# main_board.net
KiCad netlist of a schematic drawn in EAGLE
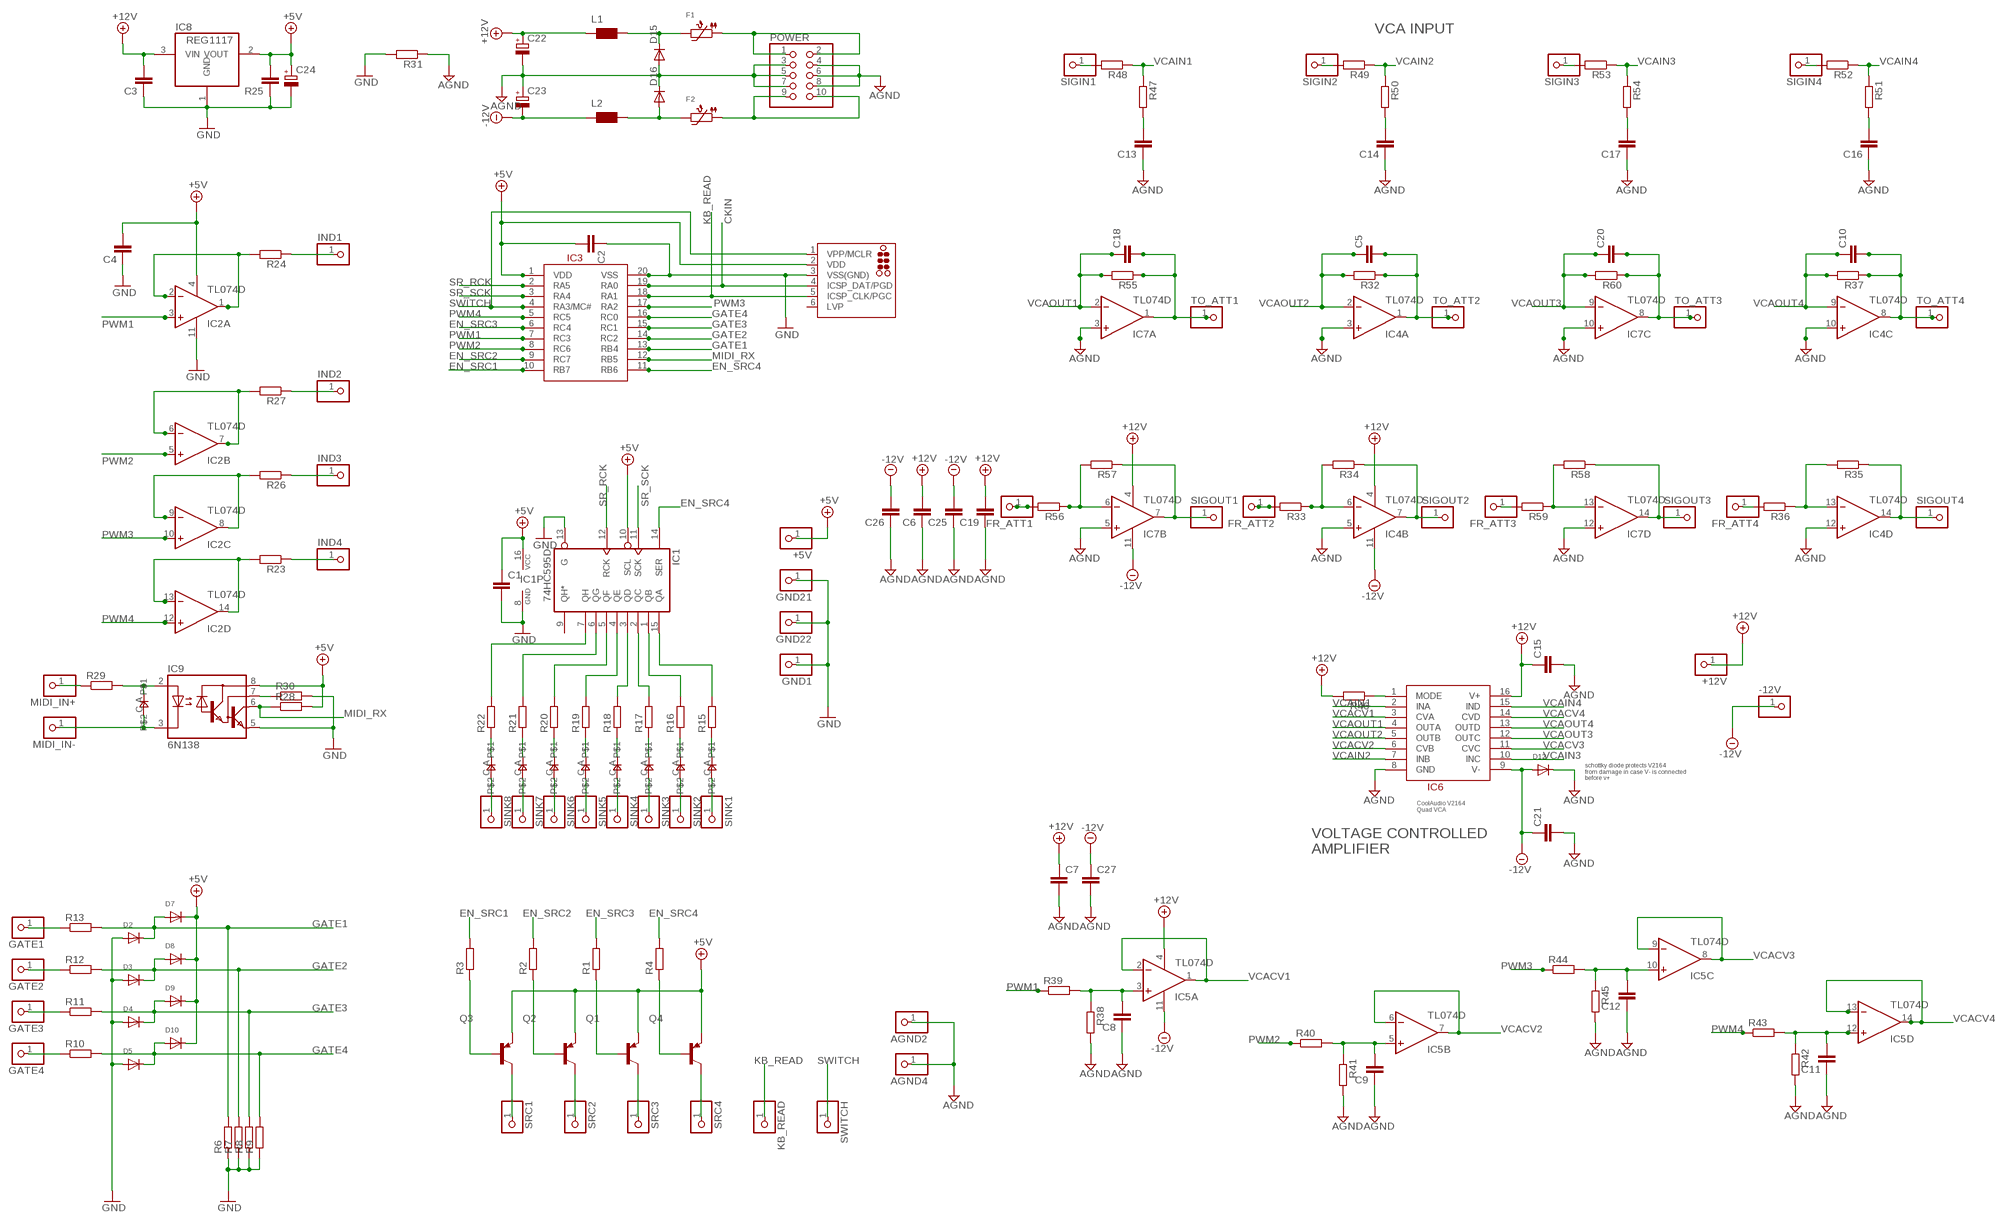
[diagram p0: schematic, sheet 1]

(export (version "E")
  (design (tool "Eeschema 10.0.6"))
  (components
    (comp (ref "+5V")
      (value "PINHD-1X1")
      (footprint "eagle-import:1X01")
      (libsource (lib "eagle-import") (part "PINHD-1X1"))
    )
    (comp (ref "+12V")
      (value "PINHD-1X1")
      (footprint "eagle-import:1X01")
      (libsource (lib "eagle-import") (part "PINHD-1X1"))
    )
    (comp (ref "-12V")
      (value "PINHD-1X1")
      (footprint "eagle-import:1X01")
      (libsource (lib "eagle-import") (part "PINHD-1X1"))
    )
    (comp (ref "AGND2")
      (value "PINHD-1X1")
      (footprint "eagle-import:1X01")
      (libsource (lib "eagle-import") (part "PINHD-1X1"))
    )
    (comp (ref "AGND4")
      (value "PINHD-1X1")
      (footprint "eagle-import:1X01")
      (libsource (lib "eagle-import") (part "PINHD-1X1"))
    )
    (comp (ref "C1")
      (value "C-EUC0805")
      (footprint "eagle-import:C0805")
      (libsource (lib "eagle-import") (part "C-EUC0805"))
    )
    (comp (ref "C2")
      (value "C-EUC0805")
      (footprint "eagle-import:C0805")
      (libsource (lib "eagle-import") (part "C-EUC0805"))
    )
    (comp (ref "C3")
      (value "C-EUC0805")
      (footprint "eagle-import:C0805")
      (libsource (lib "eagle-import") (part "C-EUC0805"))
    )
    (comp (ref "C4")
      (value "C-EUC0805")
      (footprint "eagle-import:C0805")
      (libsource (lib "eagle-import") (part "C-EUC0805"))
    )
    (comp (ref "C5")
      (value "C-EUC0805")
      (footprint "eagle-import:C0805")
      (libsource (lib "eagle-import") (part "C-EUC0805"))
    )
    (comp (ref "C6")
      (value "C-EUC0805")
      (footprint "eagle-import:C0805")
      (libsource (lib "eagle-import") (part "C-EUC0805"))
    )
    (comp (ref "C7")
      (value "C-EUC0805")
      (footprint "eagle-import:C0805")
      (libsource (lib "eagle-import") (part "C-EUC0805"))
    )
    (comp (ref "C8")
      (value "C-EUC0805")
      (footprint "eagle-import:C0805")
      (libsource (lib "eagle-import") (part "C-EUC0805"))
    )
    (comp (ref "C9")
      (value "C-EUC0805")
      (footprint "eagle-import:C0805")
      (libsource (lib "eagle-import") (part "C-EUC0805"))
    )
    (comp (ref "C10")
      (value "C-EUC0805")
      (footprint "eagle-import:C0805")
      (libsource (lib "eagle-import") (part "C-EUC0805"))
    )
    (comp (ref "C11")
      (value "C-EUC0805")
      (footprint "eagle-import:C0805")
      (libsource (lib "eagle-import") (part "C-EUC0805"))
    )
    (comp (ref "C12")
      (value "C-EUC0805")
      (footprint "eagle-import:C0805")
      (libsource (lib "eagle-import") (part "C-EUC0805"))
    )
    (comp (ref "C13")
      (value "C-EUC0805")
      (footprint "eagle-import:C0805")
      (libsource (lib "eagle-import") (part "C-EUC0805"))
    )
    (comp (ref "C14")
      (value "C-EUC0805")
      (footprint "eagle-import:C0805")
      (libsource (lib "eagle-import") (part "C-EUC0805"))
    )
    (comp (ref "C15")
      (value "C-EUC0805")
      (footprint "eagle-import:C0805")
      (libsource (lib "eagle-import") (part "C-EUC0805"))
    )
    (comp (ref "C16")
      (value "C-EUC0805")
      (footprint "eagle-import:C0805")
      (libsource (lib "eagle-import") (part "C-EUC0805"))
    )
    (comp (ref "C17")
      (value "C-EUC0805")
      (footprint "eagle-import:C0805")
      (libsource (lib "eagle-import") (part "C-EUC0805"))
    )
    (comp (ref "C18")
      (value "C-EUC0805")
      (footprint "eagle-import:C0805")
      (libsource (lib "eagle-import") (part "C-EUC0805"))
    )
    (comp (ref "C19")
      (value "C-EUC0805")
      (footprint "eagle-import:C0805")
      (libsource (lib "eagle-import") (part "C-EUC0805"))
    )
    (comp (ref "C20")
      (value "C-EUC0805")
      (footprint "eagle-import:C0805")
      (libsource (lib "eagle-import") (part "C-EUC0805"))
    )
    (comp (ref "C21")
      (value "C-EUC0805")
      (footprint "eagle-import:C0805")
      (libsource (lib "eagle-import") (part "C-EUC0805"))
    )
    (comp (ref "C22")
      (value "CPOL-EUE2.5-7")
      (footprint "eagle-import:E2,5-7")
      (libsource (lib "eagle-import") (part "CPOL-EUE2.5-7"))
    )
    (comp (ref "C23")
      (value "CPOL-EUE2.5-7")
      (footprint "eagle-import:E2,5-7")
      (libsource (lib "eagle-import") (part "CPOL-EUE2.5-7"))
    )
    (comp (ref "C24")
      (value "CPOL-EUE2.5-5")
      (footprint "eagle-import:E2,5-5")
      (libsource (lib "eagle-import") (part "CPOL-EUE2.5-5"))
    )
    (comp (ref "C25")
      (value "C-EUC0805")
      (footprint "eagle-import:C0805")
      (libsource (lib "eagle-import") (part "C-EUC0805"))
    )
    (comp (ref "C26")
      (value "C-EUC0805")
      (footprint "eagle-import:C0805")
      (libsource (lib "eagle-import") (part "C-EUC0805"))
    )
    (comp (ref "C27")
      (value "C-EUC0805")
      (footprint "eagle-import:C0805")
      (libsource (lib "eagle-import") (part "C-EUC0805"))
    )
    (comp (ref "D2")
      (value "DIODESOD-123")
      (footprint "eagle-import:SOD-123")
      (libsource (lib "eagle-import") (part "DIODESOD-123"))
    )
    (comp (ref "D3")
      (value "DIODESOD-123")
      (footprint "eagle-import:SOD-123")
      (libsource (lib "eagle-import") (part "DIODESOD-123"))
    )
    (comp (ref "D4")
      (value "DIODESOD-123")
      (footprint "eagle-import:SOD-123")
      (libsource (lib "eagle-import") (part "DIODESOD-123"))
    )
    (comp (ref "D5")
      (value "DIODESOD-123")
      (footprint "eagle-import:SOD-123")
      (libsource (lib "eagle-import") (part "DIODESOD-123"))
    )
    (comp (ref "D7")
      (value "DIODESOD-123")
      (footprint "eagle-import:SOD-123")
      (libsource (lib "eagle-import") (part "DIODESOD-123"))
    )
    (comp (ref "D8")
      (value "DIODESOD-123")
      (footprint "eagle-import:SOD-123")
      (libsource (lib "eagle-import") (part "DIODESOD-123"))
    )
    (comp (ref "D9")
      (value "DIODESOD-123")
      (footprint "eagle-import:SOD-123")
      (libsource (lib "eagle-import") (part "DIODESOD-123"))
    )
    (comp (ref "D10")
      (value "DIODESOD-123")
      (footprint "eagle-import:SOD-123")
      (libsource (lib "eagle-import") (part "DIODESOD-123"))
    )
    (comp (ref "D11")
      (value "0805DIODE")
      (footprint "eagle-import:0805DIODE")
      (libsource (lib "eagle-import") (part "0805DIODE"))
    )
    (comp (ref "D12")
      (value "DIODESOD-123")
      (footprint "eagle-import:SOD-123")
      (libsource (lib "eagle-import") (part "DIODESOD-123"))
    )
    (comp (ref "D13")
      (value "0805DIODE")
      (footprint "eagle-import:0805DIODE")
      (libsource (lib "eagle-import") (part "0805DIODE"))
    )
    (comp (ref "D14")
      (value "0805DIODE")
      (footprint "eagle-import:0805DIODE")
      (libsource (lib "eagle-import") (part "0805DIODE"))
    )
    (comp (ref "D15")
      (value "MBR0520LT")
      (footprint "eagle-import:SOD123")
      (libsource (lib "eagle-import") (part "MBR0520LT"))
    )
    (comp (ref "D16")
      (value "MBR0520LT")
      (footprint "eagle-import:SOD123")
      (libsource (lib "eagle-import") (part "MBR0520LT"))
    )
    (comp (ref "D17")
      (value "0805DIODE")
      (footprint "eagle-import:0805DIODE")
      (libsource (lib "eagle-import") (part "0805DIODE"))
    )
    (comp (ref "D18")
      (value "0805DIODE")
      (footprint "eagle-import:0805DIODE")
      (libsource (lib "eagle-import") (part "0805DIODE"))
    )
    (comp (ref "D19")
      (value "0805DIODE")
      (footprint "eagle-import:0805DIODE")
      (libsource (lib "eagle-import") (part "0805DIODE"))
    )
    (comp (ref "D20")
      (value "0805DIODE")
      (footprint "eagle-import:0805DIODE")
      (libsource (lib "eagle-import") (part "0805DIODE"))
    )
    (comp (ref "D21")
      (value "0805DIODE")
      (footprint "eagle-import:0805DIODE")
      (libsource (lib "eagle-import") (part "0805DIODE"))
    )
    (comp (ref "D22")
      (value "0805DIODE")
      (footprint "eagle-import:0805DIODE")
      (libsource (lib "eagle-import") (part "0805DIODE"))
    )
    (comp (ref "F1")
      (value "PTC1210")
      (footprint "eagle-import:PTC1210")
      (libsource (lib "eagle-import") (part "PTC1210"))
    )
    (comp (ref "F2")
      (value "PTC1210")
      (footprint "eagle-import:PTC1210")
      (libsource (lib "eagle-import") (part "PTC1210"))
    )
    (comp (ref "FR_ATT1")
      (value "PINHD-1X1")
      (footprint "eagle-import:1X01")
      (libsource (lib "eagle-import") (part "PINHD-1X1"))
    )
    (comp (ref "FR_ATT2")
      (value "PINHD-1X1")
      (footprint "eagle-import:1X01")
      (libsource (lib "eagle-import") (part "PINHD-1X1"))
    )
    (comp (ref "FR_ATT3")
      (value "PINHD-1X1")
      (footprint "eagle-import:1X01")
      (libsource (lib "eagle-import") (part "PINHD-1X1"))
    )
    (comp (ref "FR_ATT4")
      (value "PINHD-1X1")
      (footprint "eagle-import:1X01")
      (libsource (lib "eagle-import") (part "PINHD-1X1"))
    )
    (comp (ref "GATE1")
      (value "PINHD-1X1")
      (footprint "eagle-import:1X01")
      (libsource (lib "eagle-import") (part "PINHD-1X1"))
    )
    (comp (ref "GATE2")
      (value "PINHD-1X1")
      (footprint "eagle-import:1X01")
      (libsource (lib "eagle-import") (part "PINHD-1X1"))
    )
    (comp (ref "GATE3")
      (value "PINHD-1X1")
      (footprint "eagle-import:1X01")
      (libsource (lib "eagle-import") (part "PINHD-1X1"))
    )
    (comp (ref "GATE4")
      (value "PINHD-1X1")
      (footprint "eagle-import:1X01")
      (libsource (lib "eagle-import") (part "PINHD-1X1"))
    )
    (comp (ref "GND1")
      (value "PINHD-1X1")
      (footprint "eagle-import:1X01")
      (libsource (lib "eagle-import") (part "PINHD-1X1"))
    )
    (comp (ref "GND21")
      (value "PINHD-1X1")
      (footprint "eagle-import:1X01")
      (libsource (lib "eagle-import") (part "PINHD-1X1"))
    )
    (comp (ref "GND22")
      (value "PINHD-1X1")
      (footprint "eagle-import:1X01")
      (libsource (lib "eagle-import") (part "PINHD-1X1"))
    )
    (comp (ref "IC1")
      (value "74HC595D")
      (footprint "eagle-import:SO16")
      (libsource (lib "eagle-import") (part "74595DHC"))
    )
    (comp (ref "IC2")
      (value "TL074D")
      (footprint "eagle-import:SO14")
      (libsource (lib "eagle-import") (part "TL074D"))
    )
    (comp (ref "IC3")
      (value "PIC16F1829SOIC")
      (footprint "eagle-import:SO20W")
      (libsource (lib "eagle-import") (part "PIC16F1829SOIC"))
    )
    (comp (ref "IC4")
      (value "TL074D")
      (footprint "eagle-import:SO14")
      (libsource (lib "eagle-import") (part "TL074D"))
    )
    (comp (ref "IC5")
      (value "TL074D")
      (footprint "eagle-import:SO14")
      (libsource (lib "eagle-import") (part "TL074D"))
    )
    (comp (ref "IC6")
      (value "V2164")
      (footprint "eagle-import:SO16")
      (libsource (lib "eagle-import") (part "V2164"))
    )
    (comp (ref "IC7")
      (value "TL074D")
      (footprint "eagle-import:SO14")
      (libsource (lib "eagle-import") (part "TL074D"))
    )
    (comp (ref "IC8")
      (value "REG1117")
      (footprint "eagle-import:SOT223")
      (libsource (lib "eagle-import") (part "REG1117"))
    )
    (comp (ref "IC9")
      (value "6N138")
      (footprint "eagle-import:DIL08")
      (fields (field (name "MF") "VISHAY/TELEFUNKEN"))
      (libsource (lib "eagle-import") (part "6N138"))
    )
    (comp (ref "ICSP")
      (value "TC2030-MCP-NL")
      (footprint "eagle-import:TC2030-MCP-NL")
      (libsource (lib "eagle-import") (part "TC2030-MCP-NL"))
    )
    (comp (ref "IND1")
      (value "PINHD-1X1")
      (footprint "eagle-import:1X01")
      (libsource (lib "eagle-import") (part "PINHD-1X1"))
    )
    (comp (ref "IND2")
      (value "PINHD-1X1")
      (footprint "eagle-import:1X01")
      (libsource (lib "eagle-import") (part "PINHD-1X1"))
    )
    (comp (ref "IND3")
      (value "PINHD-1X1")
      (footprint "eagle-import:1X01")
      (libsource (lib "eagle-import") (part "PINHD-1X1"))
    )
    (comp (ref "IND4")
      (value "PINHD-1X1")
      (footprint "eagle-import:1X01")
      (libsource (lib "eagle-import") (part "PINHD-1X1"))
    )
    (comp (ref "KB_READ")
      (value "PINHD-1X1")
      (footprint "eagle-import:1X01")
      (libsource (lib "eagle-import") (part "PINHD-1X1"))
    )
    (comp (ref "L1")
      (value "WE-CBF_0805")
      (footprint "eagle-import:0805")
      (libsource (lib "eagle-import") (part "WE-CBF_0805"))
    )
    (comp (ref "L2")
      (value "WE-CBF_0805")
      (footprint "eagle-import:0805")
      (libsource (lib "eagle-import") (part "WE-CBF_0805"))
    )
    (comp (ref "MIDI_IN+")
      (value "PINHD-1X1")
      (footprint "eagle-import:1X01")
      (libsource (lib "eagle-import") (part "PINHD-1X1"))
    )
    (comp (ref "MIDI_IN-")
      (value "PINHD-1X1")
      (footprint "eagle-import:1X01")
      (libsource (lib "eagle-import") (part "PINHD-1X1"))
    )
    (comp (ref "POWER")
      (value "PINHD-2X5")
      (footprint "eagle-import:2X05")
      (libsource (lib "eagle-import") (part "PINHD-2X5"))
    )
    (comp (ref "Q1")
      (value "MMBT3906LT1-PNP-SOT23-BEC")
      (footprint "eagle-import:SOT23-BEC")
      (libsource (lib "eagle-import") (part "-PNP-SOT23-BECMMBT3906LT1"))
    )
    (comp (ref "Q2")
      (value "MMBT3906LT1-PNP-SOT23-BEC")
      (footprint "eagle-import:SOT23-BEC")
      (libsource (lib "eagle-import") (part "-PNP-SOT23-BECMMBT3906LT1"))
    )
    (comp (ref "Q3")
      (value "MMBT3906LT1-PNP-SOT23-BEC")
      (footprint "eagle-import:SOT23-BEC")
      (libsource (lib "eagle-import") (part "-PNP-SOT23-BECMMBT3906LT1"))
    )
    (comp (ref "Q4")
      (value "MMBT3906LT1-PNP-SOT23-BEC")
      (footprint "eagle-import:SOT23-BEC")
      (libsource (lib "eagle-import") (part "-PNP-SOT23-BECMMBT3906LT1"))
    )
    (comp (ref "R1")
      (value "R-EU_R0805")
      (footprint "eagle-import:R0805")
      (libsource (lib "eagle-import") (part "R-EU_R0805"))
    )
    (comp (ref "R2")
      (value "R-EU_R0805")
      (footprint "eagle-import:R0805")
      (libsource (lib "eagle-import") (part "R-EU_R0805"))
    )
    (comp (ref "R3")
      (value "R-EU_R0805")
      (footprint "eagle-import:R0805")
      (libsource (lib "eagle-import") (part "R-EU_R0805"))
    )
    (comp (ref "R4")
      (value "R-EU_R0805")
      (footprint "eagle-import:R0805")
      (libsource (lib "eagle-import") (part "R-EU_R0805"))
    )
    (comp (ref "R6")
      (value "R-EU_R0805")
      (footprint "eagle-import:R0805")
      (libsource (lib "eagle-import") (part "R-EU_R0805"))
    )
    (comp (ref "R7")
      (value "R-EU_R0805")
      (footprint "eagle-import:R0805")
      (libsource (lib "eagle-import") (part "R-EU_R0805"))
    )
    (comp (ref "R8")
      (value "R-EU_R0805")
      (footprint "eagle-import:R0805")
      (libsource (lib "eagle-import") (part "R-EU_R0805"))
    )
    (comp (ref "R9")
      (value "R-EU_R0805")
      (footprint "eagle-import:R0805")
      (libsource (lib "eagle-import") (part "R-EU_R0805"))
    )
    (comp (ref "R10")
      (value "R-EU_R0805")
      (footprint "eagle-import:R0805")
      (libsource (lib "eagle-import") (part "R-EU_R0805"))
    )
    (comp (ref "R11")
      (value "R-EU_R0805")
      (footprint "eagle-import:R0805")
      (libsource (lib "eagle-import") (part "R-EU_R0805"))
    )
    (comp (ref "R12")
      (value "R-EU_R0805")
      (footprint "eagle-import:R0805")
      (libsource (lib "eagle-import") (part "R-EU_R0805"))
    )
    (comp (ref "R13")
      (value "R-EU_R0805")
      (footprint "eagle-import:R0805")
      (libsource (lib "eagle-import") (part "R-EU_R0805"))
    )
    (comp (ref "R15")
      (value "R-EU_R0805")
      (footprint "eagle-import:R0805")
      (libsource (lib "eagle-import") (part "R-EU_R0805"))
    )
    (comp (ref "R16")
      (value "R-EU_R0805")
      (footprint "eagle-import:R0805")
      (libsource (lib "eagle-import") (part "R-EU_R0805"))
    )
    (comp (ref "R17")
      (value "R-EU_R0805")
      (footprint "eagle-import:R0805")
      (libsource (lib "eagle-import") (part "R-EU_R0805"))
    )
    (comp (ref "R18")
      (value "R-EU_R0805")
      (footprint "eagle-import:R0805")
      (libsource (lib "eagle-import") (part "R-EU_R0805"))
    )
    (comp (ref "R19")
      (value "R-EU_R0805")
      (footprint "eagle-import:R0805")
      (libsource (lib "eagle-import") (part "R-EU_R0805"))
    )
    (comp (ref "R20")
      (value "R-EU_R0805")
      (footprint "eagle-import:R0805")
      (libsource (lib "eagle-import") (part "R-EU_R0805"))
    )
    (comp (ref "R21")
      (value "R-EU_R0805")
      (footprint "eagle-import:R0805")
      (libsource (lib "eagle-import") (part "R-EU_R0805"))
    )
    (comp (ref "R22")
      (value "R-EU_R0805")
      (footprint "eagle-import:R0805")
      (libsource (lib "eagle-import") (part "R-EU_R0805"))
    )
    (comp (ref "R23")
      (value "R-EU_R0805")
      (footprint "eagle-import:R0805")
      (libsource (lib "eagle-import") (part "R-EU_R0805"))
    )
    (comp (ref "R24")
      (value "R-EU_R0805")
      (footprint "eagle-import:R0805")
      (libsource (lib "eagle-import") (part "R-EU_R0805"))
    )
    (comp (ref "R25")
      (value "C-EUC0805")
      (footprint "eagle-import:C0805")
      (libsource (lib "eagle-import") (part "C-EUC0805"))
    )
    (comp (ref "R26")
      (value "R-EU_R0805")
      (footprint "eagle-import:R0805")
      (libsource (lib "eagle-import") (part "R-EU_R0805"))
    )
    (comp (ref "R27")
      (value "R-EU_R0805")
      (footprint "eagle-import:R0805")
      (libsource (lib "eagle-import") (part "R-EU_R0805"))
    )
    (comp (ref "R28")
      (value "R-EU_R0805")
      (footprint "eagle-import:R0805")
      (libsource (lib "eagle-import") (part "R-EU_R0805"))
    )
    (comp (ref "R29")
      (value "R-EU_R0805")
      (footprint "eagle-import:R0805")
      (libsource (lib "eagle-import") (part "R-EU_R0805"))
    )
    (comp (ref "R30")
      (value "R-EU_R0805")
      (footprint "eagle-import:R0805")
      (libsource (lib "eagle-import") (part "R-EU_R0805"))
    )
    (comp (ref "R31")
      (value "R-EU_R0805")
      (footprint "eagle-import:R0805")
      (libsource (lib "eagle-import") (part "R-EU_R0805"))
    )
    (comp (ref "R32")
      (value "R-EU_R0805")
      (footprint "eagle-import:R0805")
      (libsource (lib "eagle-import") (part "R-EU_R0805"))
    )
    (comp (ref "R33")
      (value "R-EU_R0805")
      (footprint "eagle-import:R0805")
      (libsource (lib "eagle-import") (part "R-EU_R0805"))
    )
    (comp (ref "R34")
      (value "R-EU_R0805")
      (footprint "eagle-import:R0805")
      (libsource (lib "eagle-import") (part "R-EU_R0805"))
    )
    (comp (ref "R35")
      (value "R-EU_R0805")
      (footprint "eagle-import:R0805")
      (libsource (lib "eagle-import") (part "R-EU_R0805"))
    )
    (comp (ref "R36")
      (value "R-EU_R0805")
      (footprint "eagle-import:R0805")
      (libsource (lib "eagle-import") (part "R-EU_R0805"))
    )
    (comp (ref "R37")
      (value "R-EU_R0805")
      (footprint "eagle-import:R0805")
      (libsource (lib "eagle-import") (part "R-EU_R0805"))
    )
    (comp (ref "R38")
      (value "R-EU_R0805")
      (footprint "eagle-import:R0805")
      (libsource (lib "eagle-import") (part "R-EU_R0805"))
    )
    (comp (ref "R39")
      (value "R-EU_R0805")
      (footprint "eagle-import:R0805")
      (libsource (lib "eagle-import") (part "R-EU_R0805"))
    )
    (comp (ref "R40")
      (value "R-EU_R0805")
      (footprint "eagle-import:R0805")
      (libsource (lib "eagle-import") (part "R-EU_R0805"))
    )
    (comp (ref "R41")
      (value "R-EU_R0805")
      (footprint "eagle-import:R0805")
      (libsource (lib "eagle-import") (part "R-EU_R0805"))
    )
    (comp (ref "R42")
      (value "R-EU_R0805")
      (footprint "eagle-import:R0805")
      (libsource (lib "eagle-import") (part "R-EU_R0805"))
    )
    (comp (ref "R43")
      (value "R-EU_R0805")
      (footprint "eagle-import:R0805")
      (libsource (lib "eagle-import") (part "R-EU_R0805"))
    )
    (comp (ref "R44")
      (value "R-EU_R0805")
      (footprint "eagle-import:R0805")
      (libsource (lib "eagle-import") (part "R-EU_R0805"))
    )
    (comp (ref "R45")
      (value "R-EU_R0805")
      (footprint "eagle-import:R0805")
      (libsource (lib "eagle-import") (part "R-EU_R0805"))
    )
    (comp (ref "R46")
      (value "R-EU_R0805")
      (footprint "eagle-import:R0805")
      (libsource (lib "eagle-import") (part "R-EU_R0805"))
    )
    (comp (ref "R47")
      (value "R-EU_R0805")
      (footprint "eagle-import:R0805")
      (libsource (lib "eagle-import") (part "R-EU_R0805"))
    )
    (comp (ref "R48")
      (value "R-EU_R0805")
      (footprint "eagle-import:R0805")
      (libsource (lib "eagle-import") (part "R-EU_R0805"))
    )
    (comp (ref "R49")
      (value "R-EU_R0805")
      (footprint "eagle-import:R0805")
      (libsource (lib "eagle-import") (part "R-EU_R0805"))
    )
    (comp (ref "R50")
      (value "R-EU_R0805")
      (footprint "eagle-import:R0805")
      (libsource (lib "eagle-import") (part "R-EU_R0805"))
    )
    (comp (ref "R51")
      (value "R-EU_R0805")
      (footprint "eagle-import:R0805")
      (libsource (lib "eagle-import") (part "R-EU_R0805"))
    )
    (comp (ref "R52")
      (value "R-EU_R0805")
      (footprint "eagle-import:R0805")
      (libsource (lib "eagle-import") (part "R-EU_R0805"))
    )
    (comp (ref "R53")
      (value "R-EU_R0805")
      (footprint "eagle-import:R0805")
      (libsource (lib "eagle-import") (part "R-EU_R0805"))
    )
    (comp (ref "R54")
      (value "R-EU_R0805")
      (footprint "eagle-import:R0805")
      (libsource (lib "eagle-import") (part "R-EU_R0805"))
    )
    (comp (ref "R55")
      (value "R-EU_R0805")
      (footprint "eagle-import:R0805")
      (libsource (lib "eagle-import") (part "R-EU_R0805"))
    )
    (comp (ref "R56")
      (value "R-EU_R0805")
      (footprint "eagle-import:R0805")
      (libsource (lib "eagle-import") (part "R-EU_R0805"))
    )
    (comp (ref "R57")
      (value "R-EU_R0805")
      (footprint "eagle-import:R0805")
      (libsource (lib "eagle-import") (part "R-EU_R0805"))
    )
    (comp (ref "R58")
      (value "R-EU_R0805")
      (footprint "eagle-import:R0805")
      (libsource (lib "eagle-import") (part "R-EU_R0805"))
    )
    (comp (ref "R59")
      (value "R-EU_R0805")
      (footprint "eagle-import:R0805")
      (libsource (lib "eagle-import") (part "R-EU_R0805"))
    )
    (comp (ref "R60")
      (value "R-EU_R0805")
      (footprint "eagle-import:R0805")
      (libsource (lib "eagle-import") (part "R-EU_R0805"))
    )
    (comp (ref "SIGIN1")
      (value "PINHD-1X1")
      (footprint "eagle-import:1X01")
      (libsource (lib "eagle-import") (part "PINHD-1X1"))
    )
    (comp (ref "SIGIN2")
      (value "PINHD-1X1")
      (footprint "eagle-import:1X01")
      (libsource (lib "eagle-import") (part "PINHD-1X1"))
    )
    (comp (ref "SIGIN3")
      (value "PINHD-1X1")
      (footprint "eagle-import:1X01")
      (libsource (lib "eagle-import") (part "PINHD-1X1"))
    )
    (comp (ref "SIGIN4")
      (value "PINHD-1X1")
      (footprint "eagle-import:1X01")
      (libsource (lib "eagle-import") (part "PINHD-1X1"))
    )
    (comp (ref "SIGOUT1")
      (value "PINHD-1X1")
      (footprint "eagle-import:1X01")
      (libsource (lib "eagle-import") (part "PINHD-1X1"))
    )
    (comp (ref "SIGOUT2")
      (value "PINHD-1X1")
      (footprint "eagle-import:1X01")
      (libsource (lib "eagle-import") (part "PINHD-1X1"))
    )
    (comp (ref "SIGOUT3")
      (value "PINHD-1X1")
      (footprint "eagle-import:1X01")
      (libsource (lib "eagle-import") (part "PINHD-1X1"))
    )
    (comp (ref "SIGOUT4")
      (value "PINHD-1X1")
      (footprint "eagle-import:1X01")
      (libsource (lib "eagle-import") (part "PINHD-1X1"))
    )
    (comp (ref "SINK1")
      (value "PINHD-1X1")
      (footprint "eagle-import:1X01")
      (libsource (lib "eagle-import") (part "PINHD-1X1"))
    )
    (comp (ref "SINK2")
      (value "PINHD-1X1")
      (footprint "eagle-import:1X01")
      (libsource (lib "eagle-import") (part "PINHD-1X1"))
    )
    (comp (ref "SINK3")
      (value "PINHD-1X1")
      (footprint "eagle-import:1X01")
      (libsource (lib "eagle-import") (part "PINHD-1X1"))
    )
    (comp (ref "SINK4")
      (value "PINHD-1X1")
      (footprint "eagle-import:1X01")
      (libsource (lib "eagle-import") (part "PINHD-1X1"))
    )
    (comp (ref "SINK5")
      (value "PINHD-1X1")
      (footprint "eagle-import:1X01")
      (libsource (lib "eagle-import") (part "PINHD-1X1"))
    )
    (comp (ref "SINK6")
      (value "PINHD-1X1")
      (footprint "eagle-import:1X01")
      (libsource (lib "eagle-import") (part "PINHD-1X1"))
    )
    (comp (ref "SINK7")
      (value "PINHD-1X1")
      (footprint "eagle-import:1X01")
      (libsource (lib "eagle-import") (part "PINHD-1X1"))
    )
    (comp (ref "SINK8")
      (value "PINHD-1X1")
      (footprint "eagle-import:1X01")
      (libsource (lib "eagle-import") (part "PINHD-1X1"))
    )
    (comp (ref "SRC1")
      (value "PINHD-1X1")
      (footprint "eagle-import:1X01")
      (libsource (lib "eagle-import") (part "PINHD-1X1"))
    )
    (comp (ref "SRC2")
      (value "PINHD-1X1")
      (footprint "eagle-import:1X01")
      (libsource (lib "eagle-import") (part "PINHD-1X1"))
    )
    (comp (ref "SRC3")
      (value "PINHD-1X1")
      (footprint "eagle-import:1X01")
      (libsource (lib "eagle-import") (part "PINHD-1X1"))
    )
    (comp (ref "SRC4")
      (value "PINHD-1X1")
      (footprint "eagle-import:1X01")
      (libsource (lib "eagle-import") (part "PINHD-1X1"))
    )
    (comp (ref "SWITCH")
      (value "PINHD-1X1")
      (footprint "eagle-import:1X01")
      (libsource (lib "eagle-import") (part "PINHD-1X1"))
    )
    (comp (ref "TO_ATT1")
      (value "PINHD-1X1")
      (footprint "eagle-import:1X01")
      (libsource (lib "eagle-import") (part "PINHD-1X1"))
    )
    (comp (ref "TO_ATT2")
      (value "PINHD-1X1")
      (footprint "eagle-import:1X01")
      (libsource (lib "eagle-import") (part "PINHD-1X1"))
    )
    (comp (ref "TO_ATT3")
      (value "PINHD-1X1")
      (footprint "eagle-import:1X01")
      (libsource (lib "eagle-import") (part "PINHD-1X1"))
    )
    (comp (ref "TO_ATT4")
      (value "PINHD-1X1")
      (footprint "eagle-import:1X01")
      (libsource (lib "eagle-import") (part "PINHD-1X1"))
    )
  )
  (nets
    (net (code "1") (name "+5V") (class "Default")
      (node (ref "+5V") (pin "1") (pinfunction "1_1") (pintype "passive"))
      (node (ref "C1") (pin "1") (pinfunction "1_1") (pintype "passive"))
      (node (ref "C2") (pin "2") (pinfunction "2_2") (pintype "passive"))
      (node (ref "C24") (pin "+") (pinfunction "+_+") (pintype "passive"))
      (node (ref "C4") (pin "2") (pinfunction "2_2") (pintype "passive"))
      (node (ref "D10") (pin "C") (pinfunction "C_C") (pintype "passive"))
      (node (ref "D7") (pin "C") (pinfunction "C_C") (pintype "passive"))
      (node (ref "D8") (pin "C") (pinfunction "C_C") (pintype "passive"))
      (node (ref "D9") (pin "C") (pinfunction "C_C") (pintype "passive"))
      (node (ref "IC1") (pin "10") (pinfunction "SCL_10") (pintype "input"))
      (node (ref "IC1") (pin "16") (pinfunction "VCC_16") (pintype "power_in"))
      (node (ref "IC2") (pin "4") (pinfunction "V+_4") (pintype "power_in"))
      (node (ref "IC3") (pin "1") (pinfunction "VDD_1") (pintype "power_in"))
      (node (ref "IC8") (pin "2") (pinfunction "VOUT_2") (pintype "output"))
      (node (ref "IC9") (pin "8") (pinfunction "VCC_8") (pintype "passive"))
      (node (ref "ICSP") (pin "2") (pinfunction "VDD_2") (pintype "power_in"))
      (node (ref "Q1") (pin "E") (pinfunction "E_E") (pintype "passive"))
      (node (ref "Q2") (pin "E") (pinfunction "E_E") (pintype "passive"))
      (node (ref "Q3") (pin "E") (pinfunction "E_E") (pintype "passive"))
      (node (ref "Q4") (pin "E") (pinfunction "E_E") (pintype "passive"))
      (node (ref "R25") (pin "2") (pinfunction "2_2") (pintype "passive"))
      (node (ref "R28") (pin "2") (pinfunction "2_2") (pintype "passive"))
    )
    (net (code "2") (name "+12V") (class "Default")
      (node (ref "+12V") (pin "1") (pinfunction "1_1") (pintype "passive"))
      (node (ref "C15") (pin "1") (pinfunction "1_1") (pintype "passive"))
      (node (ref "C19") (pin "2") (pinfunction "2_2") (pintype "passive"))
      (node (ref "C22") (pin "+") (pinfunction "+_+") (pintype "passive"))
      (node (ref "C3") (pin "2") (pinfunction "2_2") (pintype "passive"))
      (node (ref "C6") (pin "2") (pinfunction "2_2") (pintype "passive"))
      (node (ref "C7") (pin "1") (pinfunction "1_1") (pintype "passive"))
      (node (ref "IC4") (pin "4") (pinfunction "V+_4") (pintype "power_in"))
      (node (ref "IC5") (pin "4") (pinfunction "V+_4") (pintype "power_in"))
      (node (ref "IC6") (pin "16") (pinfunction "V+_16") (pintype "bidirectional"))
      (node (ref "IC7") (pin "4") (pinfunction "V+_4") (pintype "power_in"))
      (node (ref "IC8") (pin "3") (pinfunction "VIN_3") (pintype "input"))
      (node (ref "L1") (pin "1") (pinfunction "1_1") (pintype "passive"))
      (node (ref "R46") (pin "2") (pinfunction "2_2") (pintype "passive"))
    )
    (net (code "3") (name "-12V") (class "Default")
      (node (ref "-12V") (pin "1") (pinfunction "1_1") (pintype "passive"))
      (node (ref "C21") (pin "1") (pinfunction "1_1") (pintype "passive"))
      (node (ref "C23") (pin "-") (pinfunction "-_-") (pintype "passive"))
      (node (ref "C25") (pin "2") (pinfunction "2_2") (pintype "passive"))
      (node (ref "C26") (pin "2") (pinfunction "2_2") (pintype "passive"))
      (node (ref "C27") (pin "1") (pinfunction "1_1") (pintype "passive"))
      (node (ref "D12") (pin "A") (pinfunction "A_A") (pintype "passive"))
      (node (ref "IC4") (pin "11") (pinfunction "V-_11") (pintype "power_in"))
      (node (ref "IC5") (pin "11") (pinfunction "V-_11") (pintype "power_in"))
      (node (ref "IC6") (pin "9") (pinfunction "V-_9") (pintype "bidirectional"))
      (node (ref "IC7") (pin "11") (pinfunction "V-_11") (pintype "power_in"))
      (node (ref "L2") (pin "1") (pinfunction "1_1") (pintype "passive"))
    )
    (net (code "4") (name "/CKIN") (class "Default")
      (node (ref "IC3") (pin "19") (pinfunction "RA0_19") (pintype "bidirectional"))
      (node (ref "ICSP") (pin "4") (pinfunction "ICSP_DAT/PGD_4") (pintype "bidirectional"))
    )
    (net (code "5") (name "/EN_SRC1") (class "Default")
      (node (ref "IC3") (pin "10") (pinfunction "RB7_10") (pintype "bidirectional"))
      (node (ref "R3") (pin "2") (pinfunction "2_2") (pintype "passive"))
    )
    (net (code "6") (name "/EN_SRC2") (class "Default")
      (node (ref "IC3") (pin "9") (pinfunction "RC7_9") (pintype "bidirectional"))
      (node (ref "R2") (pin "2") (pinfunction "2_2") (pintype "passive"))
    )
    (net (code "7") (name "/EN_SRC3") (class "Default")
      (node (ref "IC3") (pin "6") (pinfunction "RC4_6") (pintype "bidirectional"))
      (node (ref "R1") (pin "2") (pinfunction "2_2") (pintype "passive"))
    )
    (net (code "8") (name "/EN_SRC4") (class "Default")
      (node (ref "IC1") (pin "14") (pinfunction "SER_14") (pintype "input"))
      (node (ref "IC3") (pin "11") (pinfunction "RB6_11") (pintype "bidirectional"))
      (node (ref "R4") (pin "2") (pinfunction "2_2") (pintype "passive"))
    )
    (net (code "9") (name "/GATE1") (class "Default")
      (node (ref "D2") (pin "C") (pinfunction "C_C") (pintype "passive"))
      (node (ref "D7") (pin "A") (pinfunction "A_A") (pintype "passive"))
      (node (ref "IC3") (pin "13") (pinfunction "RB4_13") (pintype "bidirectional"))
      (node (ref "R13") (pin "2") (pinfunction "2_2") (pintype "passive"))
      (node (ref "R6") (pin "2") (pinfunction "2_2") (pintype "passive"))
    )
    (net (code "10") (name "/GATE2") (class "Default")
      (node (ref "D3") (pin "C") (pinfunction "C_C") (pintype "passive"))
      (node (ref "D8") (pin "A") (pinfunction "A_A") (pintype "passive"))
      (node (ref "IC3") (pin "14") (pinfunction "RC2_14") (pintype "bidirectional"))
      (node (ref "R12") (pin "2") (pinfunction "2_2") (pintype "passive"))
      (node (ref "R7") (pin "2") (pinfunction "2_2") (pintype "passive"))
    )
    (net (code "11") (name "/GATE3") (class "Default")
      (node (ref "D4") (pin "C") (pinfunction "C_C") (pintype "passive"))
      (node (ref "D9") (pin "A") (pinfunction "A_A") (pintype "passive"))
      (node (ref "IC3") (pin "15") (pinfunction "RC1_15") (pintype "bidirectional"))
      (node (ref "R11") (pin "2") (pinfunction "2_2") (pintype "passive"))
      (node (ref "R8") (pin "2") (pinfunction "2_2") (pintype "passive"))
    )
    (net (code "12") (name "/GATE4") (class "Default")
      (node (ref "D10") (pin "A") (pinfunction "A_A") (pintype "passive"))
      (node (ref "D5") (pin "C") (pinfunction "C_C") (pintype "passive"))
      (node (ref "IC3") (pin "16") (pinfunction "RC0_16") (pintype "bidirectional"))
      (node (ref "R10") (pin "2") (pinfunction "2_2") (pintype "passive"))
      (node (ref "R9") (pin "2") (pinfunction "2_2") (pintype "passive"))
    )
    (net (code "13") (name "/KB_READ") (class "Default")
      (node (ref "IC3") (pin "18") (pinfunction "RA1_18") (pintype "bidirectional"))
      (node (ref "ICSP") (pin "5") (pinfunction "ICSP_CLK/PGC_5") (pintype "output"))
      (node (ref "KB_READ") (pin "1") (pinfunction "1_1") (pintype "passive"))
    )
    (net (code "14") (name "/MIDI_RX") (class "Default")
      (node (ref "IC3") (pin "12") (pinfunction "RB5_12") (pintype "bidirectional"))
      (node (ref "IC9") (pin "6") (pinfunction "VO_6") (pintype "passive"))
      (node (ref "R28") (pin "1") (pinfunction "1_1") (pintype "passive"))
    )
    (net (code "15") (name "/PWM1") (class "Default")
      (node (ref "IC2") (pin "3") (pinfunction "+IN_3") (pintype "input"))
      (node (ref "IC3") (pin "7") (pinfunction "RC3_7") (pintype "bidirectional"))
      (node (ref "R39") (pin "1") (pinfunction "1_1") (pintype "passive"))
    )
    (net (code "16") (name "/PWM2") (class "Default")
      (node (ref "IC2") (pin "5") (pinfunction "+IN_5") (pintype "input"))
      (node (ref "IC3") (pin "8") (pinfunction "RC6_8") (pintype "bidirectional"))
      (node (ref "R40") (pin "1") (pinfunction "1_1") (pintype "passive"))
    )
    (net (code "17") (name "/PWM3") (class "Default")
      (node (ref "IC2") (pin "10") (pinfunction "+IN_10") (pintype "input"))
      (node (ref "IC3") (pin "17") (pinfunction "RA2_17") (pintype "bidirectional"))
      (node (ref "R44") (pin "1") (pinfunction "1_1") (pintype "passive"))
    )
    (net (code "18") (name "/PWM4") (class "Default")
      (node (ref "IC2") (pin "12") (pinfunction "+IN_12") (pintype "input"))
      (node (ref "IC3") (pin "5") (pinfunction "RC5_5") (pintype "bidirectional"))
      (node (ref "R43") (pin "1") (pinfunction "1_1") (pintype "passive"))
    )
    (net (code "19") (name "/SR_RCK") (class "Default")
      (node (ref "IC1") (pin "12") (pinfunction "RCK_12") (pintype "input"))
      (node (ref "IC3") (pin "2") (pinfunction "RA5_2") (pintype "bidirectional"))
    )
    (net (code "20") (name "/SR_SCK") (class "Default")
      (node (ref "IC1") (pin "11") (pinfunction "SCK_11") (pintype "input"))
      (node (ref "IC3") (pin "3") (pinfunction "RA4_3") (pintype "bidirectional"))
    )
    (net (code "21") (name "/SWITCH") (class "Default")
      (node (ref "IC3") (pin "4") (pinfunction "RA3/MC#_4") (pintype "bidirectional"))
      (node (ref "ICSP") (pin "1") (pinfunction "VPP/MCLR_1") (pintype "passive"))
      (node (ref "SWITCH") (pin "1") (pinfunction "1_1") (pintype "passive"))
    )
    (net (code "22") (name "/VCACV1") (class "Default")
      (node (ref "IC5") (pin "1") (pinfunction "OUT_1") (pintype "output"))
      (node (ref "IC5") (pin "2") (pinfunction "-IN_2") (pintype "input"))
      (node (ref "IC6") (pin "3") (pinfunction "CVA_3") (pintype "bidirectional"))
    )
    (net (code "23") (name "/VCACV2") (class "Default")
      (node (ref "IC5") (pin "6") (pinfunction "-IN_6") (pintype "input"))
      (node (ref "IC5") (pin "7") (pinfunction "OUT_7") (pintype "output"))
      (node (ref "IC6") (pin "6") (pinfunction "CVB_6") (pintype "bidirectional"))
    )
    (net (code "24") (name "/VCACV3") (class "Default")
      (node (ref "IC5") (pin "8") (pinfunction "OUT_8") (pintype "output"))
      (node (ref "IC5") (pin "9") (pinfunction "-IN_9") (pintype "input"))
      (node (ref "IC6") (pin "11") (pinfunction "CVC_11") (pintype "bidirectional"))
    )
    (net (code "25") (name "/VCACV4") (class "Default")
      (node (ref "IC5") (pin "13") (pinfunction "-IN_13") (pintype "input"))
      (node (ref "IC5") (pin "14") (pinfunction "OUT_14") (pintype "output"))
      (node (ref "IC6") (pin "14") (pinfunction "CVD_14") (pintype "bidirectional"))
    )
    (net (code "26") (name "/VCAIN1") (class "Default")
      (node (ref "IC6") (pin "2") (pinfunction "INA_2") (pintype "bidirectional"))
      (node (ref "R47") (pin "1") (pinfunction "1_1") (pintype "passive"))
      (node (ref "R48") (pin "1") (pinfunction "1_1") (pintype "passive"))
    )
    (net (code "27") (name "/VCAIN2") (class "Default")
      (node (ref "IC6") (pin "7") (pinfunction "INB_7") (pintype "bidirectional"))
      (node (ref "R49") (pin "1") (pinfunction "1_1") (pintype "passive"))
      (node (ref "R50") (pin "1") (pinfunction "1_1") (pintype "passive"))
    )
    (net (code "28") (name "/VCAIN3") (class "Default")
      (node (ref "IC6") (pin "10") (pinfunction "INC_10") (pintype "bidirectional"))
      (node (ref "R53") (pin "1") (pinfunction "1_1") (pintype "passive"))
      (node (ref "R54") (pin "1") (pinfunction "1_1") (pintype "passive"))
    )
    (net (code "29") (name "/VCAIN4") (class "Default")
      (node (ref "IC6") (pin "15") (pinfunction "IND_15") (pintype "bidirectional"))
      (node (ref "R51") (pin "1") (pinfunction "1_1") (pintype "passive"))
      (node (ref "R52") (pin "1") (pinfunction "1_1") (pintype "passive"))
    )
    (net (code "30") (name "/VCAOUT1") (class "Default")
      (node (ref "C18") (pin "1") (pinfunction "1_1") (pintype "passive"))
      (node (ref "IC6") (pin "4") (pinfunction "OUTA_4") (pintype "bidirectional"))
      (node (ref "IC7") (pin "2") (pinfunction "-IN_2") (pintype "input"))
      (node (ref "R55") (pin "2") (pinfunction "2_2") (pintype "passive"))
    )
    (net (code "31") (name "/VCAOUT2") (class "Default")
      (node (ref "C5") (pin "1") (pinfunction "1_1") (pintype "passive"))
      (node (ref "IC4") (pin "2") (pinfunction "-IN_2") (pintype "input"))
      (node (ref "IC6") (pin "5") (pinfunction "OUTB_5") (pintype "bidirectional"))
      (node (ref "R32") (pin "2") (pinfunction "2_2") (pintype "passive"))
    )
    (net (code "32") (name "/VCAOUT3") (class "Default")
      (node (ref "C20") (pin "1") (pinfunction "1_1") (pintype "passive"))
      (node (ref "IC6") (pin "12") (pinfunction "OUTC_12") (pintype "bidirectional"))
      (node (ref "IC7") (pin "9") (pinfunction "-IN_9") (pintype "input"))
      (node (ref "R60") (pin "2") (pinfunction "2_2") (pintype "passive"))
    )
    (net (code "33") (name "/VCAOUT4") (class "Default")
      (node (ref "C10") (pin "1") (pinfunction "1_1") (pintype "passive"))
      (node (ref "IC4") (pin "9") (pinfunction "-IN_9") (pintype "input"))
      (node (ref "IC6") (pin "13") (pinfunction "OUTD_13") (pintype "bidirectional"))
      (node (ref "R37") (pin "2") (pinfunction "2_2") (pintype "passive"))
    )
    (net (code "34") (name "AGND") (class "Default")
      (node (ref "AGND2") (pin "1") (pinfunction "1_1") (pintype "passive"))
      (node (ref "AGND4") (pin "1") (pinfunction "1_1") (pintype "passive"))
      (node (ref "C11") (pin "1") (pinfunction "1_1") (pintype "passive"))
      (node (ref "C12") (pin "1") (pinfunction "1_1") (pintype "passive"))
      (node (ref "C13") (pin "1") (pinfunction "1_1") (pintype "passive"))
      (node (ref "C14") (pin "1") (pinfunction "1_1") (pintype "passive"))
      (node (ref "C15") (pin "2") (pinfunction "2_2") (pintype "passive"))
      (node (ref "C16") (pin "1") (pinfunction "1_1") (pintype "passive"))
      (node (ref "C17") (pin "1") (pinfunction "1_1") (pintype "passive"))
      (node (ref "C19") (pin "1") (pinfunction "1_1") (pintype "passive"))
      (node (ref "C21") (pin "2") (pinfunction "2_2") (pintype "passive"))
      (node (ref "C22") (pin "-") (pinfunction "-_-") (pintype "passive"))
      (node (ref "C23") (pin "+") (pinfunction "+_+") (pintype "passive"))
      (node (ref "C25") (pin "1") (pinfunction "1_1") (pintype "passive"))
      (node (ref "C26") (pin "1") (pinfunction "1_1") (pintype "passive"))
      (node (ref "C27") (pin "2") (pinfunction "2_2") (pintype "passive"))
      (node (ref "C6") (pin "1") (pinfunction "1_1") (pintype "passive"))
      (node (ref "C7") (pin "2") (pinfunction "2_2") (pintype "passive"))
      (node (ref "C8") (pin "1") (pinfunction "1_1") (pintype "passive"))
      (node (ref "C9") (pin "1") (pinfunction "1_1") (pintype "passive"))
      (node (ref "D12") (pin "C") (pinfunction "C_C") (pintype "passive"))
      (node (ref "D15") (pin "A") (pinfunction "A_A") (pintype "passive"))
      (node (ref "D16") (pin "C") (pinfunction "C_C") (pintype "passive"))
      (node (ref "IC4") (pin "10") (pinfunction "+IN_10") (pintype "input"))
      (node (ref "IC4") (pin "12") (pinfunction "+IN_12") (pintype "input"))
      (node (ref "IC4") (pin "3") (pinfunction "+IN_3") (pintype "input"))
      (node (ref "IC4") (pin "5") (pinfunction "+IN_5") (pintype "input"))
      (node (ref "IC6") (pin "8") (pinfunction "GND_8") (pintype "bidirectional"))
      (node (ref "IC7") (pin "10") (pinfunction "+IN_10") (pintype "input"))
      (node (ref "IC7") (pin "12") (pinfunction "+IN_12") (pintype "input"))
      (node (ref "IC7") (pin "3") (pinfunction "+IN_3") (pintype "input"))
      (node (ref "IC7") (pin "5") (pinfunction "+IN_5") (pintype "input"))
      (node (ref "POWER") (pin "3") (pinfunction "3_3") (pintype "passive"))
      (node (ref "POWER") (pin "4") (pinfunction "4_4") (pintype "passive"))
      (node (ref "POWER") (pin "5") (pinfunction "5_5") (pintype "passive"))
      (node (ref "POWER") (pin "6") (pinfunction "6_6") (pintype "passive"))
      (node (ref "POWER") (pin "7") (pinfunction "7_7") (pintype "passive"))
      (node (ref "POWER") (pin "8") (pinfunction "8_8") (pintype "passive"))
      (node (ref "R31") (pin "1") (pinfunction "1_1") (pintype "passive"))
      (node (ref "R38") (pin "2") (pinfunction "2_2") (pintype "passive"))
      (node (ref "R41") (pin "2") (pinfunction "2_2") (pintype "passive"))
      (node (ref "R42") (pin "2") (pinfunction "2_2") (pintype "passive"))
      (node (ref "R45") (pin "2") (pinfunction "2_2") (pintype "passive"))
    )
    (net (code "35") (name "GND") (class "Default")
      (node (ref "C1") (pin "2") (pinfunction "2_2") (pintype "passive"))
      (node (ref "C2") (pin "1") (pinfunction "1_1") (pintype "passive"))
      (node (ref "C24") (pin "-") (pinfunction "-_-") (pintype "passive"))
      (node (ref "C3") (pin "1") (pinfunction "1_1") (pintype "passive"))
      (node (ref "C4") (pin "1") (pinfunction "1_1") (pintype "passive"))
      (node (ref "D2") (pin "A") (pinfunction "A_A") (pintype "passive"))
      (node (ref "D3") (pin "A") (pinfunction "A_A") (pintype "passive"))
      (node (ref "D4") (pin "A") (pinfunction "A_A") (pintype "passive"))
      (node (ref "D5") (pin "A") (pinfunction "A_A") (pintype "passive"))
      (node (ref "GND1") (pin "1") (pinfunction "1_1") (pintype "passive"))
      (node (ref "GND21") (pin "1") (pinfunction "1_1") (pintype "passive"))
      (node (ref "GND22") (pin "1") (pinfunction "1_1") (pintype "passive"))
      (node (ref "IC1") (pin "13") (pinfunction "G_13") (pintype "input"))
      (node (ref "IC1") (pin "8") (pinfunction "GND_8") (pintype "power_in"))
      (node (ref "IC2") (pin "11") (pinfunction "V-_11") (pintype "power_in"))
      (node (ref "IC3") (pin "20") (pinfunction "VSS_20") (pintype "power_in"))
      (node (ref "IC8") (pin "1") (pinfunction "GND_1") (pintype "power_in"))
      (node (ref "IC9") (pin "5") (pinfunction "GND_5") (pintype "passive"))
      (node (ref "ICSP") (pin "3") (pinfunction "VSS(GND)_3") (pintype "power_in"))
      (node (ref "R25") (pin "1") (pinfunction "1_1") (pintype "passive"))
      (node (ref "R30") (pin "2") (pinfunction "2_2") (pintype "passive"))
      (node (ref "R31") (pin "2") (pinfunction "2_2") (pintype "passive"))
      (node (ref "R6") (pin "1") (pinfunction "1_1") (pintype "passive"))
      (node (ref "R7") (pin "1") (pinfunction "1_1") (pintype "passive"))
      (node (ref "R8") (pin "1") (pinfunction "1_1") (pintype "passive"))
      (node (ref "R9") (pin "1") (pinfunction "1_1") (pintype "passive"))
    )
    (net (code "36") (name "Net-(C13-Pad2)") (class "Default")
      (node (ref "C13") (pin "2") (pinfunction "2_2") (pintype "passive"))
      (node (ref "R47") (pin "2") (pinfunction "2_2") (pintype "passive"))
    )
    (net (code "37") (name "Net-(C14-Pad2)") (class "Default")
      (node (ref "C14") (pin "2") (pinfunction "2_2") (pintype "passive"))
      (node (ref "R50") (pin "2") (pinfunction "2_2") (pintype "passive"))
    )
    (net (code "38") (name "Net-(C16-Pad2)") (class "Default")
      (node (ref "C16") (pin "2") (pinfunction "2_2") (pintype "passive"))
      (node (ref "R51") (pin "2") (pinfunction "2_2") (pintype "passive"))
    )
    (net (code "39") (name "Net-(C17-Pad2)") (class "Default")
      (node (ref "C17") (pin "2") (pinfunction "2_2") (pintype "passive"))
      (node (ref "R54") (pin "2") (pinfunction "2_2") (pintype "passive"))
    )
    (net (code "40") (name "Net-(D11-P$1)") (class "Default")
      (node (ref "D11") (pin "C") (pinfunction "P$1_C") (pintype "bidirectional"))
      (node (ref "IC9") (pin "3") (pinfunction "C_3") (pintype "passive"))
      (node (ref "MIDI_IN-") (pin "1") (pinfunction "1_1") (pintype "passive"))
    )
    (net (code "41") (name "Net-(D11-P$2)") (class "Default")
      (node (ref "D11") (pin "A") (pinfunction "P$2_A") (pintype "bidirectional"))
      (node (ref "IC9") (pin "2") (pinfunction "A_2") (pintype "passive"))
      (node (ref "R29") (pin "2") (pinfunction "2_2") (pintype "passive"))
    )
    (net (code "42") (name "Net-(D13-P$1)") (class "Default")
      (node (ref "D13") (pin "C") (pinfunction "P$1_C") (pintype "bidirectional"))
      (node (ref "SINK8") (pin "1") (pinfunction "1_1") (pintype "passive"))
    )
    (net (code "43") (name "Net-(D13-P$2)") (class "Default")
      (node (ref "D13") (pin "A") (pinfunction "P$2_A") (pintype "bidirectional"))
      (node (ref "R22") (pin "1") (pinfunction "1_1") (pintype "passive"))
    )
    (net (code "44") (name "Net-(D14-P$1)") (class "Default")
      (node (ref "D14") (pin "C") (pinfunction "P$1_C") (pintype "bidirectional"))
      (node (ref "SINK7") (pin "1") (pinfunction "1_1") (pintype "passive"))
    )
    (net (code "45") (name "Net-(D14-P$2)") (class "Default")
      (node (ref "D14") (pin "A") (pinfunction "P$2_A") (pintype "bidirectional"))
      (node (ref "R21") (pin "1") (pinfunction "1_1") (pintype "passive"))
    )
    (net (code "46") (name "Net-(D17-P$1)") (class "Default")
      (node (ref "D17") (pin "C") (pinfunction "P$1_C") (pintype "bidirectional"))
      (node (ref "SINK6") (pin "1") (pinfunction "1_1") (pintype "passive"))
    )
    (net (code "47") (name "Net-(D17-P$2)") (class "Default")
      (node (ref "D17") (pin "A") (pinfunction "P$2_A") (pintype "bidirectional"))
      (node (ref "R20") (pin "1") (pinfunction "1_1") (pintype "passive"))
    )
    (net (code "48") (name "Net-(D18-P$1)") (class "Default")
      (node (ref "D18") (pin "C") (pinfunction "P$1_C") (pintype "bidirectional"))
      (node (ref "SINK5") (pin "1") (pinfunction "1_1") (pintype "passive"))
    )
    (net (code "49") (name "Net-(D18-P$2)") (class "Default")
      (node (ref "D18") (pin "A") (pinfunction "P$2_A") (pintype "bidirectional"))
      (node (ref "R19") (pin "1") (pinfunction "1_1") (pintype "passive"))
    )
    (net (code "50") (name "Net-(D19-P$1)") (class "Default")
      (node (ref "D19") (pin "C") (pinfunction "P$1_C") (pintype "bidirectional"))
      (node (ref "SINK4") (pin "1") (pinfunction "1_1") (pintype "passive"))
    )
    (net (code "51") (name "Net-(D19-P$2)") (class "Default")
      (node (ref "D19") (pin "A") (pinfunction "P$2_A") (pintype "bidirectional"))
      (node (ref "R18") (pin "1") (pinfunction "1_1") (pintype "passive"))
    )
    (net (code "52") (name "Net-(D20-P$1)") (class "Default")
      (node (ref "D20") (pin "C") (pinfunction "P$1_C") (pintype "bidirectional"))
      (node (ref "SINK3") (pin "1") (pinfunction "1_1") (pintype "passive"))
    )
    (net (code "53") (name "Net-(D20-P$2)") (class "Default")
      (node (ref "D20") (pin "A") (pinfunction "P$2_A") (pintype "bidirectional"))
      (node (ref "R17") (pin "1") (pinfunction "1_1") (pintype "passive"))
    )
    (net (code "54") (name "Net-(D21-P$1)") (class "Default")
      (node (ref "D21") (pin "C") (pinfunction "P$1_C") (pintype "bidirectional"))
      (node (ref "SINK2") (pin "1") (pinfunction "1_1") (pintype "passive"))
    )
    (net (code "55") (name "Net-(D21-P$2)") (class "Default")
      (node (ref "D21") (pin "A") (pinfunction "P$2_A") (pintype "bidirectional"))
      (node (ref "R16") (pin "1") (pinfunction "1_1") (pintype "passive"))
    )
    (net (code "56") (name "Net-(D22-P$1)") (class "Default")
      (node (ref "D22") (pin "C") (pinfunction "P$1_C") (pintype "bidirectional"))
      (node (ref "SINK1") (pin "1") (pinfunction "1_1") (pintype "passive"))
    )
    (net (code "57") (name "Net-(D22-P$2)") (class "Default")
      (node (ref "D22") (pin "A") (pinfunction "P$2_A") (pintype "bidirectional"))
      (node (ref "R15") (pin "1") (pinfunction "1_1") (pintype "passive"))
    )
    (net (code "58") (name "Net-(F1-1)") (class "Default")
      (node (ref "F1") (pin "P$1") (pinfunction "1_P$1") (pintype "passive"))
      (node (ref "POWER") (pin "1") (pinfunction "1_1") (pintype "passive"))
      (node (ref "POWER") (pin "2") (pinfunction "2_2") (pintype "passive"))
    )
    (net (code "59") (name "Net-(F1-2)") (class "Default")
      (node (ref "D15") (pin "C") (pinfunction "C_C") (pintype "passive"))
      (node (ref "F1") (pin "P$2") (pinfunction "2_P$2") (pintype "passive"))
      (node (ref "L1") (pin "2") (pinfunction "2_2") (pintype "passive"))
    )
    (net (code "60") (name "Net-(F2-1)") (class "Default")
      (node (ref "F2") (pin "P$1") (pinfunction "1_P$1") (pintype "passive"))
      (node (ref "POWER") (pin "10") (pinfunction "10_10") (pintype "passive"))
      (node (ref "POWER") (pin "9") (pinfunction "9_9") (pintype "passive"))
    )
    (net (code "61") (name "Net-(F2-2)") (class "Default")
      (node (ref "D16") (pin "A") (pinfunction "A_A") (pintype "passive"))
      (node (ref "F2") (pin "P$2") (pinfunction "2_P$2") (pintype "passive"))
      (node (ref "L2") (pin "2") (pinfunction "2_2") (pintype "passive"))
    )
    (net (code "62") (name "Net-(FR_ATT1-Pad1)") (class "Default")
      (node (ref "FR_ATT1") (pin "1") (pinfunction "1_1") (pintype "passive"))
      (node (ref "R56") (pin "2") (pinfunction "2_2") (pintype "passive"))
    )
    (net (code "63") (name "Net-(FR_ATT2-Pad1)") (class "Default")
      (node (ref "FR_ATT2") (pin "1") (pinfunction "1_1") (pintype "passive"))
      (node (ref "R33") (pin "2") (pinfunction "2_2") (pintype "passive"))
    )
    (net (code "64") (name "Net-(FR_ATT3-Pad1)") (class "Default")
      (node (ref "FR_ATT3") (pin "1") (pinfunction "1_1") (pintype "passive"))
      (node (ref "R59") (pin "2") (pinfunction "2_2") (pintype "passive"))
    )
    (net (code "65") (name "Net-(FR_ATT4-Pad1)") (class "Default")
      (node (ref "FR_ATT4") (pin "1") (pinfunction "1_1") (pintype "passive"))
      (node (ref "R36") (pin "2") (pinfunction "2_2") (pintype "passive"))
    )
    (net (code "66") (name "Net-(GATE1-Pad1)") (class "Default")
      (node (ref "GATE1") (pin "1") (pinfunction "1_1") (pintype "passive"))
      (node (ref "R13") (pin "1") (pinfunction "1_1") (pintype "passive"))
    )
    (net (code "67") (name "Net-(GATE2-Pad1)") (class "Default")
      (node (ref "GATE2") (pin "1") (pinfunction "1_1") (pintype "passive"))
      (node (ref "R12") (pin "1") (pinfunction "1_1") (pintype "passive"))
    )
    (net (code "68") (name "Net-(GATE3-Pad1)") (class "Default")
      (node (ref "GATE3") (pin "1") (pinfunction "1_1") (pintype "passive"))
      (node (ref "R11") (pin "1") (pinfunction "1_1") (pintype "passive"))
    )
    (net (code "69") (name "Net-(GATE4-Pad1)") (class "Default")
      (node (ref "GATE4") (pin "1") (pinfunction "1_1") (pintype "passive"))
      (node (ref "R10") (pin "1") (pinfunction "1_1") (pintype "passive"))
    )
    (net (code "70") (name "Net-(IC1A-QA)") (class "Default")
      (node (ref "IC1") (pin "15") (pinfunction "QA_15") (pintype "tri_state"))
      (node (ref "R15") (pin "2") (pinfunction "2_2") (pintype "passive"))
    )
    (net (code "71") (name "Net-(IC1A-QB)") (class "Default")
      (node (ref "IC1") (pin "1") (pinfunction "QB_1") (pintype "tri_state"))
      (node (ref "R16") (pin "2") (pinfunction "2_2") (pintype "passive"))
    )
    (net (code "72") (name "Net-(IC1A-QC)") (class "Default")
      (node (ref "IC1") (pin "2") (pinfunction "QC_2") (pintype "tri_state"))
      (node (ref "R17") (pin "2") (pinfunction "2_2") (pintype "passive"))
    )
    (net (code "73") (name "Net-(IC1A-QD)") (class "Default")
      (node (ref "IC1") (pin "3") (pinfunction "QD_3") (pintype "tri_state"))
      (node (ref "R18") (pin "2") (pinfunction "2_2") (pintype "passive"))
    )
    (net (code "74") (name "Net-(IC1A-QE)") (class "Default")
      (node (ref "IC1") (pin "4") (pinfunction "QE_4") (pintype "tri_state"))
      (node (ref "R19") (pin "2") (pinfunction "2_2") (pintype "passive"))
    )
    (net (code "75") (name "Net-(IC1A-QF)") (class "Default")
      (node (ref "IC1") (pin "5") (pinfunction "QF_5") (pintype "tri_state"))
      (node (ref "R20") (pin "2") (pinfunction "2_2") (pintype "passive"))
    )
    (net (code "76") (name "Net-(IC1A-QG)") (class "Default")
      (node (ref "IC1") (pin "6") (pinfunction "QG_6") (pintype "tri_state"))
      (node (ref "R21") (pin "2") (pinfunction "2_2") (pintype "passive"))
    )
    (net (code "77") (name "Net-(IC1A-QH)") (class "Default")
      (node (ref "IC1") (pin "7") (pinfunction "QH_7") (pintype "tri_state"))
      (node (ref "R22") (pin "2") (pinfunction "2_2") (pintype "passive"))
    )
    (net (code "78") (name "Net-(IC2A--IN)") (class "Default")
      (node (ref "IC2") (pin "1") (pinfunction "OUT_1") (pintype "output"))
      (node (ref "IC2") (pin "2") (pinfunction "-IN_2") (pintype "input"))
      (node (ref "R24") (pin "2") (pinfunction "2_2") (pintype "passive"))
    )
    (net (code "79") (name "Net-(IC2B--IN)") (class "Default")
      (node (ref "IC2") (pin "6") (pinfunction "-IN_6") (pintype "input"))
      (node (ref "IC2") (pin "7") (pinfunction "OUT_7") (pintype "output"))
      (node (ref "R27") (pin "2") (pinfunction "2_2") (pintype "passive"))
    )
    (net (code "80") (name "Net-(IC2C--IN)") (class "Default")
      (node (ref "IC2") (pin "8") (pinfunction "OUT_8") (pintype "output"))
      (node (ref "IC2") (pin "9") (pinfunction "-IN_9") (pintype "input"))
      (node (ref "R26") (pin "2") (pinfunction "2_2") (pintype "passive"))
    )
    (net (code "81") (name "Net-(IC2D--IN)") (class "Default")
      (node (ref "IC2") (pin "13") (pinfunction "-IN_13") (pintype "input"))
      (node (ref "IC2") (pin "14") (pinfunction "OUT_14") (pintype "output"))
      (node (ref "R23") (pin "2") (pinfunction "2_2") (pintype "passive"))
    )
    (net (code "82") (name "Net-(IC4A-OUT)") (class "Default")
      (node (ref "C5") (pin "2") (pinfunction "2_2") (pintype "passive"))
      (node (ref "IC4") (pin "1") (pinfunction "OUT_1") (pintype "output"))
      (node (ref "R32") (pin "1") (pinfunction "1_1") (pintype "passive"))
      (node (ref "TO_ATT2") (pin "1") (pinfunction "1_1") (pintype "passive"))
    )
    (net (code "83") (name "Net-(IC4B--IN)") (class "Default")
      (node (ref "IC4") (pin "6") (pinfunction "-IN_6") (pintype "input"))
      (node (ref "R33") (pin "1") (pinfunction "1_1") (pintype "passive"))
      (node (ref "R34") (pin "2") (pinfunction "2_2") (pintype "passive"))
    )
    (net (code "84") (name "Net-(IC4B-OUT)") (class "Default")
      (node (ref "IC4") (pin "7") (pinfunction "OUT_7") (pintype "output"))
      (node (ref "R34") (pin "1") (pinfunction "1_1") (pintype "passive"))
      (node (ref "SIGOUT2") (pin "1") (pinfunction "1_1") (pintype "passive"))
    )
    (net (code "85") (name "Net-(IC4C-OUT)") (class "Default")
      (node (ref "C10") (pin "2") (pinfunction "2_2") (pintype "passive"))
      (node (ref "IC4") (pin "8") (pinfunction "OUT_8") (pintype "output"))
      (node (ref "R37") (pin "1") (pinfunction "1_1") (pintype "passive"))
      (node (ref "TO_ATT4") (pin "1") (pinfunction "1_1") (pintype "passive"))
    )
    (net (code "86") (name "Net-(IC4D--IN)") (class "Default")
      (node (ref "IC4") (pin "13") (pinfunction "-IN_13") (pintype "input"))
      (node (ref "R35") (pin "2") (pinfunction "2_2") (pintype "passive"))
      (node (ref "R36") (pin "1") (pinfunction "1_1") (pintype "passive"))
    )
    (net (code "87") (name "Net-(IC4D-OUT)") (class "Default")
      (node (ref "IC4") (pin "14") (pinfunction "OUT_14") (pintype "output"))
      (node (ref "R35") (pin "1") (pinfunction "1_1") (pintype "passive"))
      (node (ref "SIGOUT4") (pin "1") (pinfunction "1_1") (pintype "passive"))
    )
    (net (code "88") (name "Net-(IC5A-+IN)") (class "Default")
      (node (ref "C8") (pin "2") (pinfunction "2_2") (pintype "passive"))
      (node (ref "IC5") (pin "3") (pinfunction "+IN_3") (pintype "input"))
      (node (ref "R38") (pin "1") (pinfunction "1_1") (pintype "passive"))
      (node (ref "R39") (pin "2") (pinfunction "2_2") (pintype "passive"))
    )
    (net (code "89") (name "Net-(IC5B-+IN)") (class "Default")
      (node (ref "C9") (pin "2") (pinfunction "2_2") (pintype "passive"))
      (node (ref "IC5") (pin "5") (pinfunction "+IN_5") (pintype "input"))
      (node (ref "R40") (pin "2") (pinfunction "2_2") (pintype "passive"))
      (node (ref "R41") (pin "1") (pinfunction "1_1") (pintype "passive"))
    )
    (net (code "90") (name "Net-(IC5C-+IN)") (class "Default")
      (node (ref "C12") (pin "2") (pinfunction "2_2") (pintype "passive"))
      (node (ref "IC5") (pin "10") (pinfunction "+IN_10") (pintype "input"))
      (node (ref "R44") (pin "2") (pinfunction "2_2") (pintype "passive"))
      (node (ref "R45") (pin "1") (pinfunction "1_1") (pintype "passive"))
    )
    (net (code "91") (name "Net-(IC5D-+IN)") (class "Default")
      (node (ref "C11") (pin "2") (pinfunction "2_2") (pintype "passive"))
      (node (ref "IC5") (pin "12") (pinfunction "+IN_12") (pintype "input"))
      (node (ref "R42") (pin "1") (pinfunction "1_1") (pintype "passive"))
      (node (ref "R43") (pin "2") (pinfunction "2_2") (pintype "passive"))
    )
    (net (code "92") (name "Net-(IC6-MODE)") (class "Default")
      (node (ref "IC6") (pin "1") (pinfunction "MODE_1") (pintype "bidirectional"))
      (node (ref "R46") (pin "1") (pinfunction "1_1") (pintype "passive"))
    )
    (net (code "93") (name "Net-(IC7A-OUT)") (class "Default")
      (node (ref "C18") (pin "2") (pinfunction "2_2") (pintype "passive"))
      (node (ref "IC7") (pin "1") (pinfunction "OUT_1") (pintype "output"))
      (node (ref "R55") (pin "1") (pinfunction "1_1") (pintype "passive"))
      (node (ref "TO_ATT1") (pin "1") (pinfunction "1_1") (pintype "passive"))
    )
    (net (code "94") (name "Net-(IC7B--IN)") (class "Default")
      (node (ref "IC7") (pin "6") (pinfunction "-IN_6") (pintype "input"))
      (node (ref "R56") (pin "1") (pinfunction "1_1") (pintype "passive"))
      (node (ref "R57") (pin "2") (pinfunction "2_2") (pintype "passive"))
    )
    (net (code "95") (name "Net-(IC7B-OUT)") (class "Default")
      (node (ref "IC7") (pin "7") (pinfunction "OUT_7") (pintype "output"))
      (node (ref "R57") (pin "1") (pinfunction "1_1") (pintype "passive"))
      (node (ref "SIGOUT1") (pin "1") (pinfunction "1_1") (pintype "passive"))
    )
    (net (code "96") (name "Net-(IC7C-OUT)") (class "Default")
      (node (ref "C20") (pin "2") (pinfunction "2_2") (pintype "passive"))
      (node (ref "IC7") (pin "8") (pinfunction "OUT_8") (pintype "output"))
      (node (ref "R60") (pin "1") (pinfunction "1_1") (pintype "passive"))
      (node (ref "TO_ATT3") (pin "1") (pinfunction "1_1") (pintype "passive"))
    )
    (net (code "97") (name "Net-(IC7D--IN)") (class "Default")
      (node (ref "IC7") (pin "13") (pinfunction "-IN_13") (pintype "input"))
      (node (ref "R58") (pin "2") (pinfunction "2_2") (pintype "passive"))
      (node (ref "R59") (pin "1") (pinfunction "1_1") (pintype "passive"))
    )
    (net (code "98") (name "Net-(IC7D-OUT)") (class "Default")
      (node (ref "IC7") (pin "14") (pinfunction "OUT_14") (pintype "output"))
      (node (ref "R58") (pin "1") (pinfunction "1_1") (pintype "passive"))
      (node (ref "SIGOUT3") (pin "1") (pinfunction "1_1") (pintype "passive"))
    )
    (net (code "99") (name "Net-(IC9-VB)") (class "Default")
      (node (ref "IC9") (pin "7") (pinfunction "VB_7") (pintype "passive"))
      (node (ref "R30") (pin "1") (pinfunction "1_1") (pintype "passive"))
    )
    (net (code "100") (name "Net-(IND1-Pad1)") (class "Default")
      (node (ref "IND1") (pin "1") (pinfunction "1_1") (pintype "passive"))
      (node (ref "R24") (pin "1") (pinfunction "1_1") (pintype "passive"))
    )
    (net (code "101") (name "Net-(IND2-Pad1)") (class "Default")
      (node (ref "IND2") (pin "1") (pinfunction "1_1") (pintype "passive"))
      (node (ref "R27") (pin "1") (pinfunction "1_1") (pintype "passive"))
    )
    (net (code "102") (name "Net-(IND3-Pad1)") (class "Default")
      (node (ref "IND3") (pin "1") (pinfunction "1_1") (pintype "passive"))
      (node (ref "R26") (pin "1") (pinfunction "1_1") (pintype "passive"))
    )
    (net (code "103") (name "Net-(IND4-Pad1)") (class "Default")
      (node (ref "IND4") (pin "1") (pinfunction "1_1") (pintype "passive"))
      (node (ref "R23") (pin "1") (pinfunction "1_1") (pintype "passive"))
    )
    (net (code "104") (name "Net-(MIDI_IN+-Pad1)") (class "Default")
      (node (ref "MIDI_IN+") (pin "1") (pinfunction "1_1") (pintype "passive"))
      (node (ref "R29") (pin "1") (pinfunction "1_1") (pintype "passive"))
    )
    (net (code "105") (name "Net-(Q1-PadB)") (class "Default")
      (node (ref "Q1") (pin "B") (pinfunction "B_B") (pintype "passive"))
      (node (ref "R1") (pin "1") (pinfunction "1_1") (pintype "passive"))
    )
    (net (code "106") (name "Net-(Q1-PadC)") (class "Default")
      (node (ref "Q1") (pin "C") (pinfunction "C_C") (pintype "passive"))
      (node (ref "SRC3") (pin "1") (pinfunction "1_1") (pintype "passive"))
    )
    (net (code "107") (name "Net-(Q2-PadB)") (class "Default")
      (node (ref "Q2") (pin "B") (pinfunction "B_B") (pintype "passive"))
      (node (ref "R2") (pin "1") (pinfunction "1_1") (pintype "passive"))
    )
    (net (code "108") (name "Net-(Q2-PadC)") (class "Default")
      (node (ref "Q2") (pin "C") (pinfunction "C_C") (pintype "passive"))
      (node (ref "SRC2") (pin "1") (pinfunction "1_1") (pintype "passive"))
    )
    (net (code "109") (name "Net-(Q3-PadB)") (class "Default")
      (node (ref "Q3") (pin "B") (pinfunction "B_B") (pintype "passive"))
      (node (ref "R3") (pin "1") (pinfunction "1_1") (pintype "passive"))
    )
    (net (code "110") (name "Net-(Q3-PadC)") (class "Default")
      (node (ref "Q3") (pin "C") (pinfunction "C_C") (pintype "passive"))
      (node (ref "SRC1") (pin "1") (pinfunction "1_1") (pintype "passive"))
    )
    (net (code "111") (name "Net-(Q4-PadB)") (class "Default")
      (node (ref "Q4") (pin "B") (pinfunction "B_B") (pintype "passive"))
      (node (ref "R4") (pin "1") (pinfunction "1_1") (pintype "passive"))
    )
    (net (code "112") (name "Net-(Q4-PadC)") (class "Default")
      (node (ref "Q4") (pin "C") (pinfunction "C_C") (pintype "passive"))
      (node (ref "SRC4") (pin "1") (pinfunction "1_1") (pintype "passive"))
    )
    (net (code "113") (name "Net-(R48-Pad2)") (class "Default")
      (node (ref "R48") (pin "2") (pinfunction "2_2") (pintype "passive"))
      (node (ref "SIGIN1") (pin "1") (pinfunction "1_1") (pintype "passive"))
    )
    (net (code "114") (name "Net-(R49-Pad2)") (class "Default")
      (node (ref "R49") (pin "2") (pinfunction "2_2") (pintype "passive"))
      (node (ref "SIGIN2") (pin "1") (pinfunction "1_1") (pintype "passive"))
    )
    (net (code "115") (name "Net-(R52-Pad2)") (class "Default")
      (node (ref "R52") (pin "2") (pinfunction "2_2") (pintype "passive"))
      (node (ref "SIGIN4") (pin "1") (pinfunction "1_1") (pintype "passive"))
    )
    (net (code "116") (name "Net-(R53-Pad2)") (class "Default")
      (node (ref "R53") (pin "2") (pinfunction "2_2") (pintype "passive"))
      (node (ref "SIGIN3") (pin "1") (pinfunction "1_1") (pintype "passive"))
    )
    (net (code "117") (name "unconnected-(IC1A-QH*-Pad9)") (class "Default")
      (node (ref "IC1") (pin "9") (pinfunction "QH*_9") (pintype "tri_state"))
    )
    (net (code "118") (name "unconnected-(ICSP-LVP-Pad6)") (class "Default")
      (node (ref "ICSP") (pin "6") (pinfunction "LVP_6") (pintype "bidirectional"))
    )
  )
)
